# Qwiic_LoRa.net
KiCad netlist of a schematic drawn in EAGLE
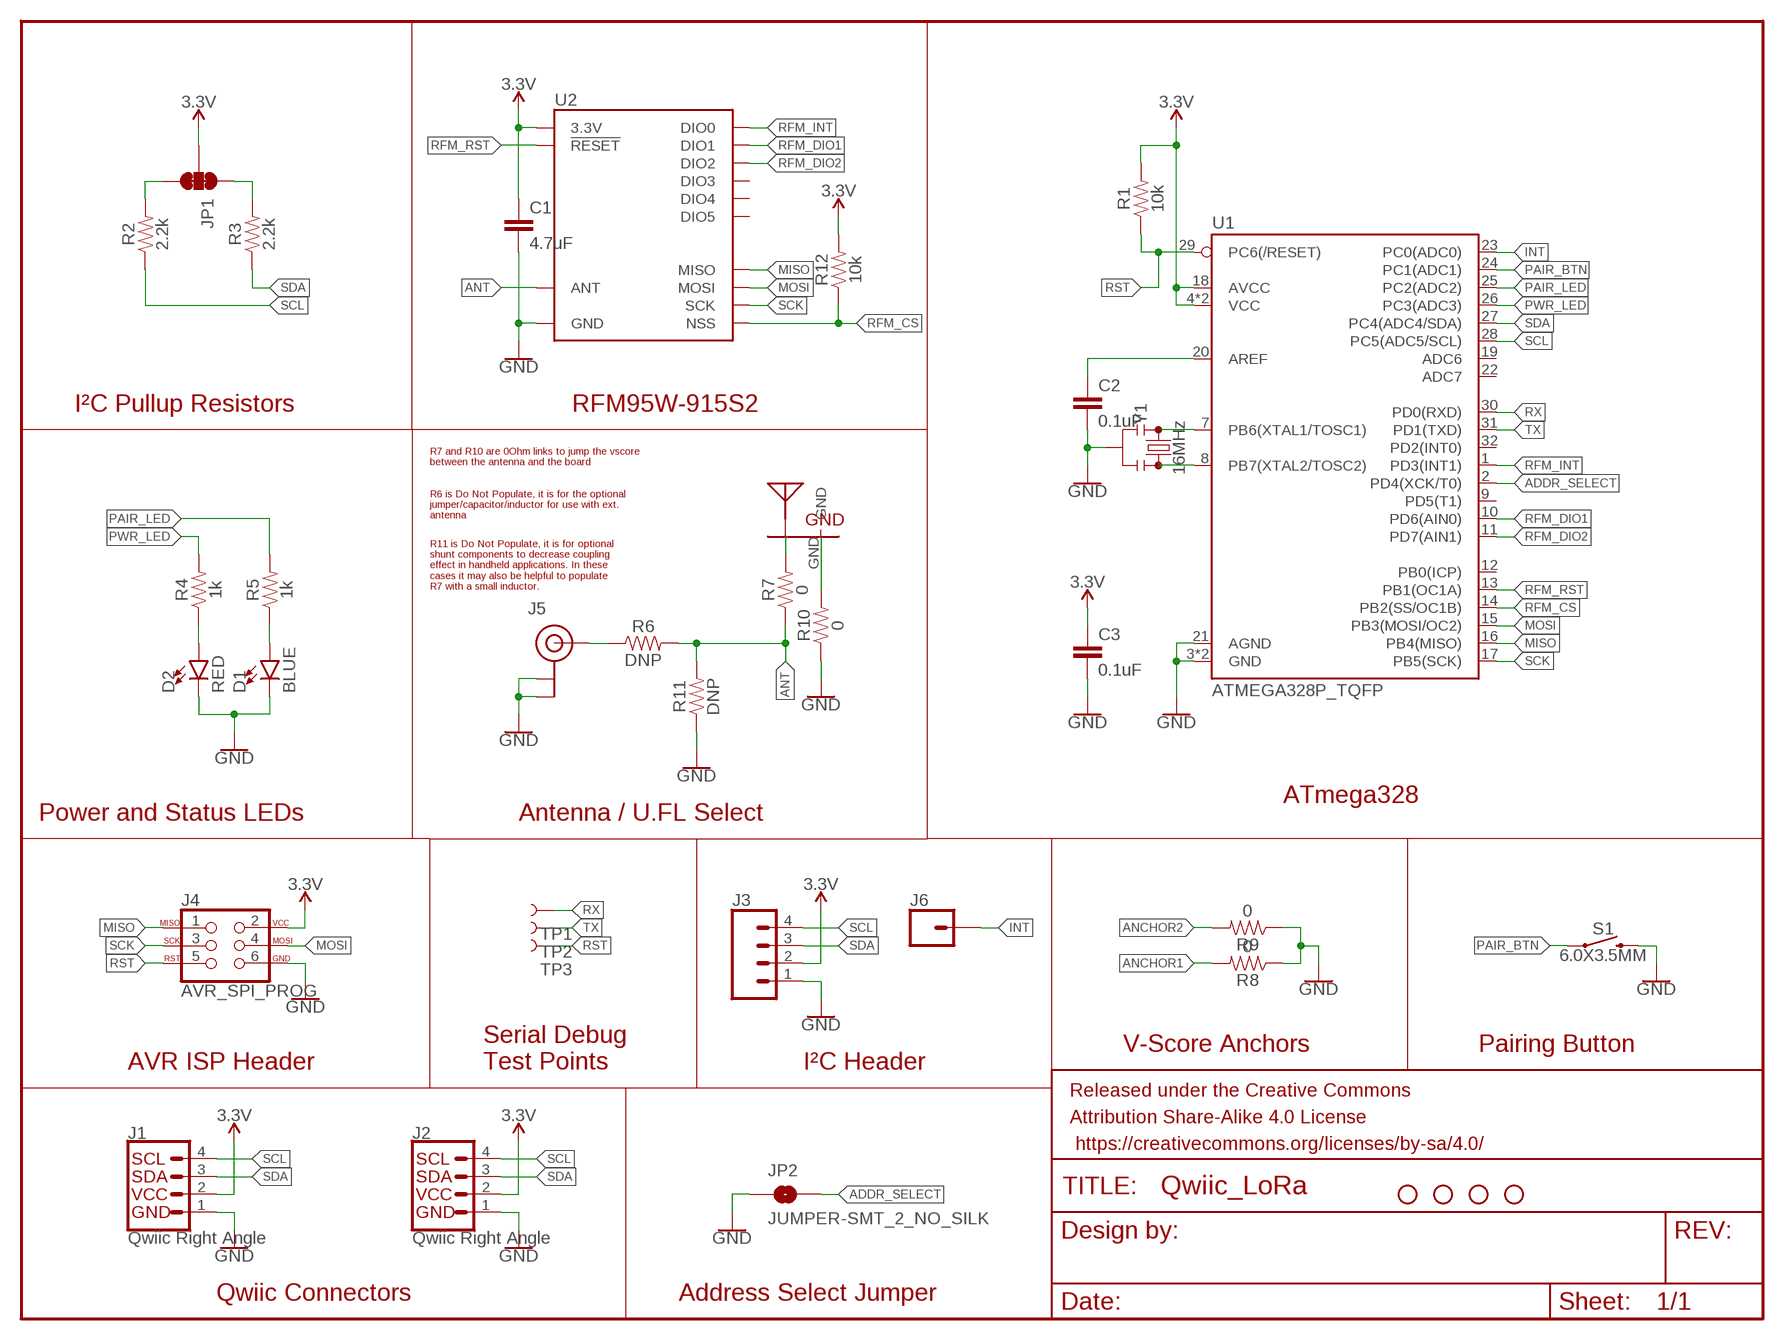
[diagram p0: schematic, sheet 1]

(export (version "E")
  (design (tool "Eeschema 10.0.6"))
  (components
    (comp (ref "C1")
      (value "4.7uF")
      (footprint "eagle-import:0603")
      (libsource (lib "eagle-import") (part "4.7UF0603"))
    )
    (comp (ref "C2")
      (value "0.1uF")
      (footprint "eagle-import:0603")
      (libsource (lib "eagle-import") (part "0.1UF-0603-25V-(+80/-20%)"))
    )
    (comp (ref "C3")
      (value "0.1uF")
      (footprint "eagle-import:0603")
      (libsource (lib "eagle-import") (part "0.1UF-0603-25V-(+80/-20%)"))
    )
    (comp (ref "D1")
      (value "BLUE")
      (footprint "eagle-import:LED-0603")
      (libsource (lib "eagle-import") (part "LED-BLUE0603"))
    )
    (comp (ref "D2")
      (value "RED")
      (footprint "eagle-import:LED-0603")
      (libsource (lib "eagle-import") (part "LED-RED0603"))
    )
    (comp (ref "FRAME1")
      (value "FRAME-LETTER")
      (footprint "eagle-import:CREATIVE_COMMONS")
      (libsource (lib "eagle-import") (part "FRAME-LETTER"))
    )
    (comp (ref "H1")
      (value "STAND-OFF")
      (footprint "eagle-import:STAND-OFF")
      (libsource (lib "eagle-import") (part "STAND-OFF"))
    )
    (comp (ref "H2")
      (value "STAND-OFF")
      (footprint "eagle-import:STAND-OFF")
      (libsource (lib "eagle-import") (part "STAND-OFF"))
    )
    (comp (ref "H3")
      (value "STAND-OFF")
      (footprint "eagle-import:STAND-OFF")
      (libsource (lib "eagle-import") (part "STAND-OFF"))
    )
    (comp (ref "H4")
      (value "STAND-OFF")
      (footprint "eagle-import:STAND-OFF")
      (libsource (lib "eagle-import") (part "STAND-OFF"))
    )
    (comp (ref "J1")
      (value "Qwiic Right Angle")
      (footprint "eagle-import:1X04_1MM_RA")
      (libsource (lib "eagle-import") (part "I2C_STANDARDQWIIC"))
    )
    (comp (ref "J2")
      (value "Qwiic Right Angle")
      (footprint "eagle-import:1X04_1MM_RA")
      (libsource (lib "eagle-import") (part "I2C_STANDARDQWIIC"))
    )
    (comp (ref "J3")
      (value "CONN_041X04_NO_SILK")
      (footprint "eagle-import:1X04_NO_SILK")
      (libsource (lib "eagle-import") (part "CONN_041X04_NO_SILK"))
    )
    (comp (ref "J4")
      (value "AVR_SPI_PROG")
      (footprint "eagle-import:2X3_TEST_POINTS")
      (libsource (lib "eagle-import") (part "AVR_SPI_PROG_3X2TESTPOINTS"))
    )
    (comp (ref "J5")
      (value "U.FL")
      (footprint "eagle-import:U.FL")
      (libsource (lib "eagle-import") (part "U.FL"))
    )
    (comp (ref "J6")
      (value "CONN_01PTH_NO_SILK_YES_STOP")
      (footprint "eagle-import:1X01_NO_SILK")
      (libsource (lib "eagle-import") (part "CONN_01PTH_NO_SILK_YES_STOP"))
    )
    (comp (ref "JP1")
      (value "JUMPER-SMT_3_2-NC_TRACE_SILK")
      (footprint "eagle-import:SMT-JUMPER_3_2-NC_TRACE_SILK")
      (libsource (lib "eagle-import") (part "JUMPER-SMT_3_2-NC_TRACE_SILK"))
    )
    (comp (ref "JP2")
      (value "JUMPER-SMT_2_NO_SILK")
      (footprint "eagle-import:SMT-JUMPER_2_NO_SILK")
      (libsource (lib "eagle-import") (part "JUMPER-SMT_2_NO_SILK"))
    )
    (comp (ref "R1")
      (value "10k")
      (footprint "eagle-import:0603")
      (libsource (lib "eagle-import") (part "10KOHM-0603-1/10W-1%"))
    )
    (comp (ref "R2")
      (value "2.2k")
      (footprint "eagle-import:0603")
      (libsource (lib "eagle-import") (part "2.2KOHM-0603-1/10W-1%"))
    )
    (comp (ref "R3")
      (value "2.2k")
      (footprint "eagle-import:0603")
      (libsource (lib "eagle-import") (part "2.2KOHM-0603-1/10W-1%"))
    )
    (comp (ref "R4")
      (value "1k")
      (footprint "eagle-import:0603")
      (libsource (lib "eagle-import") (part "1KOHM-0603-1/10W-1%"))
    )
    (comp (ref "R5")
      (value "1k")
      (footprint "eagle-import:0603")
      (libsource (lib "eagle-import") (part "1KOHM-0603-1/10W-1%"))
    )
    (comp (ref "R6")
      (value "DNP")
      (footprint "eagle-import:0603")
      (libsource (lib "eagle-import") (part "RESISTOR0603"))
    )
    (comp (ref "R7")
      (value "0")
      (footprint "eagle-import:0603")
      (libsource (lib "eagle-import") (part "RESISTOR0603"))
    )
    (comp (ref "R8")
      (value "0")
      (footprint "eagle-import:0603")
      (libsource (lib "eagle-import") (part "RESISTOR0603"))
    )
    (comp (ref "R9")
      (value "0")
      (footprint "eagle-import:0603")
      (libsource (lib "eagle-import") (part "RESISTOR0603"))
    )
    (comp (ref "R10")
      (value "0")
      (footprint "eagle-import:0603")
      (libsource (lib "eagle-import") (part "RESISTOR0603"))
    )
    (comp (ref "R11")
      (value "DNP")
      (footprint "eagle-import:0603")
      (libsource (lib "eagle-import") (part "RESISTOR0603"))
    )
    (comp (ref "R12")
      (value "10k")
      (footprint "eagle-import:0603")
      (libsource (lib "eagle-import") (part "10KOHM-0603-1/10W-1%"))
    )
    (comp (ref "S1")
      (value "6.0X3.5MM")
      (footprint "eagle-import:TACTILE_SWITCH_SMD_6.0X3.5MM")
      (libsource (lib "eagle-import") (part "MOMENTARY-SWITCH-SPST-SMD-6.0X3.5MM"))
    )
    (comp (ref "TP1")
      (value "TEST-POINT3")
      (footprint "eagle-import:PAD.03X.03")
      (libsource (lib "eagle-import") (part "TEST-POINT3"))
    )
    (comp (ref "TP2")
      (value "TEST-POINT3")
      (footprint "eagle-import:PAD.03X.03")
      (libsource (lib "eagle-import") (part "TEST-POINT3"))
    )
    (comp (ref "TP3")
      (value "TEST-POINT3")
      (footprint "eagle-import:PAD.03X.03")
      (libsource (lib "eagle-import") (part "TEST-POINT3"))
    )
    (comp (ref "U$1")
      (value "ANTENNA_915MHZ_INVERTED_F")
      (footprint "eagle-import:ANTENNA_INVERTED_F_915MHZ")
      (libsource (lib "eagle-import") (part "ANTENNA_915MHZ_INVERTED_F"))
    )
    (comp (ref "U1")
      (value "ATMEGA328P_TQFP")
      (footprint "eagle-import:TQFP32-08")
      (libsource (lib "eagle-import") (part "ATMEGA328P_TQFP"))
    )
    (comp (ref "U2")
      (value "RFM96W")
      (footprint "eagle-import:RFM95_96_97_98W")
      (libsource (lib "eagle-import") (part "RFM96W"))
    )
    (comp (ref "Y1")
      (value "16MHz")
      (footprint "eagle-import:RESONATOR-SMD-3.2X1.3")
      (libsource (lib "eagle-import") (part "RESONATOR-16MHZSMD_3.2X1.3"))
    )
  )
  (nets
    (net (code "1") (name "3.3V") (class "Default")
      (node (ref "C1") (pin "1") (pinfunction "1_1") (pintype "passive"))
      (node (ref "C3") (pin "1") (pinfunction "1_1") (pintype "passive"))
      (node (ref "J1") (pin "2") (pinfunction "2_2") (pintype "power_in"))
      (node (ref "J2") (pin "2") (pinfunction "2_2") (pintype "power_in"))
      (node (ref "J3") (pin "2") (pinfunction "2_2") (pintype "passive"))
      (node (ref "J4") (pin "2") (pinfunction "2_2") (pintype "passive"))
      (node (ref "JP1") (pin "2") (pinfunction "2_2") (pintype "passive"))
      (node (ref "R1") (pin "2") (pinfunction "2_2") (pintype "passive"))
      (node (ref "R12") (pin "2") (pinfunction "2_2") (pintype "passive"))
      (node (ref "U1") (pin "18") (pinfunction "AVCC_18") (pintype "bidirectional"))
      (node (ref "U1") (pin "4") (pinfunction "VCC_4") (pintype "bidirectional"))
      (node (ref "U1") (pin "6") (pinfunction "VCC_6") (pintype "bidirectional"))
      (node (ref "U2") (pin "3.3V") (pinfunction "3.3V_3.3V") (pintype "bidirectional"))
    )
    (net (code "2") (name "ADDR_SELECT") (class "Default")
      (node (ref "JP2") (pin "2") (pinfunction "2_2") (pintype "passive"))
      (node (ref "U1") (pin "2") (pinfunction "PD4(XCK/T0)_2") (pintype "bidirectional"))
    )
    (net (code "3") (name "ANCHOR1") (class "Default")
      (node (ref "R8") (pin "2") (pinfunction "2_2") (pintype "passive"))
    )
    (net (code "4") (name "ANCHOR2") (class "Default")
      (node (ref "R9") (pin "2") (pinfunction "2_2") (pintype "passive"))
    )
    (net (code "5") (name "ANT") (class "Default")
      (node (ref "R11") (pin "2") (pinfunction "2_2") (pintype "passive"))
      (node (ref "R6") (pin "2") (pinfunction "2_2") (pintype "passive"))
      (node (ref "R7") (pin "1") (pinfunction "1_1") (pintype "passive"))
      (node (ref "U2") (pin "ANT") (pinfunction "ANT_ANT") (pintype "bidirectional"))
    )
    (net (code "6") (name "GND") (class "Default")
      (node (ref "C1") (pin "2") (pinfunction "2_2") (pintype "passive"))
      (node (ref "C2") (pin "2") (pinfunction "2_2") (pintype "passive"))
      (node (ref "C3") (pin "2") (pinfunction "2_2") (pintype "passive"))
      (node (ref "D1") (pin "C") (pinfunction "C_C") (pintype "passive"))
      (node (ref "D2") (pin "C") (pinfunction "C_C") (pintype "passive"))
      (node (ref "J1") (pin "1") (pinfunction "1_1") (pintype "power_in"))
      (node (ref "J2") (pin "1") (pinfunction "1_1") (pintype "power_in"))
      (node (ref "J3") (pin "1") (pinfunction "1_1") (pintype "passive"))
      (node (ref "J4") (pin "6") (pinfunction "6_6") (pintype "passive"))
      (node (ref "J5") (pin "1") (pinfunction "GND_1") (pintype "bidirectional"))
      (node (ref "J5") (pin "2") (pinfunction "GND_2") (pintype "bidirectional"))
      (node (ref "JP2") (pin "1") (pinfunction "1_1") (pintype "passive"))
      (node (ref "R10") (pin "1") (pinfunction "1_1") (pintype "passive"))
      (node (ref "R11") (pin "1") (pinfunction "1_1") (pintype "passive"))
      (node (ref "R8") (pin "1") (pinfunction "1_1") (pintype "passive"))
      (node (ref "R9") (pin "1") (pinfunction "1_1") (pintype "passive"))
      (node (ref "S1") (pin "2") (pinfunction "2_2") (pintype "passive"))
      (node (ref "U1") (pin "21") (pinfunction "AGND_21") (pintype "bidirectional"))
      (node (ref "U1") (pin "3") (pinfunction "GND_3") (pintype "bidirectional"))
      (node (ref "U1") (pin "5") (pinfunction "GND_5") (pintype "bidirectional"))
      (node (ref "U2") (pin "GND@1") (pinfunction "GND_GND@1") (pintype "bidirectional"))
      (node (ref "U2") (pin "GND@2") (pinfunction "GND_GND@2") (pintype "bidirectional"))
      (node (ref "U2") (pin "GND@3") (pinfunction "GND_GND@3") (pintype "bidirectional"))
      (node (ref "Y1") (pin "2") (pinfunction "2_2") (pintype "passive"))
    )
    (net (code "7") (name "INT") (class "Default")
      (node (ref "J6") (pin "1") (pinfunction "1_1") (pintype "passive"))
      (node (ref "U1") (pin "23") (pinfunction "PC0(ADC0)_23") (pintype "bidirectional"))
    )
    (net (code "8") (name "MISO") (class "Default")
      (node (ref "J4") (pin "1") (pinfunction "1_1") (pintype "passive"))
      (node (ref "U1") (pin "16") (pinfunction "PB4(MISO)_16") (pintype "bidirectional"))
      (node (ref "U2") (pin "MISO") (pinfunction "MISO_MISO") (pintype "bidirectional"))
    )
    (net (code "9") (name "MOSI") (class "Default")
      (node (ref "J4") (pin "4") (pinfunction "4_4") (pintype "passive"))
      (node (ref "U1") (pin "15") (pinfunction "PB3(MOSI/OC2)_15") (pintype "bidirectional"))
      (node (ref "U2") (pin "MOSI") (pinfunction "MOSI_MOSI") (pintype "bidirectional"))
    )
    (net (code "10") (name "Net-(D1-PadA)") (class "Default")
      (node (ref "D1") (pin "A") (pinfunction "A_A") (pintype "passive"))
      (node (ref "R5") (pin "1") (pinfunction "1_1") (pintype "passive"))
    )
    (net (code "11") (name "Net-(D2-PadA)") (class "Default")
      (node (ref "D2") (pin "A") (pinfunction "A_A") (pintype "passive"))
      (node (ref "R4") (pin "1") (pinfunction "1_1") (pintype "passive"))
    )
    (net (code "12") (name "Net-(J5-SIGNAL)") (class "Default")
      (node (ref "J5") (pin "FEED") (pinfunction "SIGNAL_FEED") (pintype "bidirectional"))
      (node (ref "R6") (pin "1") (pinfunction "1_1") (pintype "passive"))
    )
    (net (code "13") (name "Net-(JP1-Pad1)") (class "Default")
      (node (ref "JP1") (pin "1") (pinfunction "1_1") (pintype "passive"))
      (node (ref "R3") (pin "2") (pinfunction "2_2") (pintype "passive"))
    )
    (net (code "14") (name "Net-(JP1-Pad3)") (class "Default")
      (node (ref "JP1") (pin "3") (pinfunction "3_3") (pintype "passive"))
      (node (ref "R2") (pin "2") (pinfunction "2_2") (pintype "passive"))
    )
    (net (code "15") (name "Net-(R7-Pad2)") (class "Default")
      (node (ref "R7") (pin "2") (pinfunction "2_2") (pintype "passive"))
      (node (ref "U$1") (pin "FEED") (pinfunction "FEED_FEED") (pintype "bidirectional"))
    )
    (net (code "16") (name "Net-(R10-Pad2)") (class "Default")
      (node (ref "R10") (pin "2") (pinfunction "2_2") (pintype "passive"))
      (node (ref "U$1") (pin "GND") (pinfunction "GND_GND") (pintype "bidirectional"))
    )
    (net (code "17") (name "Net-(U1-AREF)") (class "Default")
      (node (ref "C2") (pin "1") (pinfunction "1_1") (pintype "passive"))
      (node (ref "U1") (pin "20") (pinfunction "AREF_20") (pintype "bidirectional"))
    )
    (net (code "18") (name "Net-(U1-PB6(XTAL1{slash}TOSC1))") (class "Default")
      (node (ref "U1") (pin "7") (pinfunction "PB6(XTAL1/TOSC1)_7") (pintype "bidirectional"))
      (node (ref "Y1") (pin "1") (pinfunction "1_1") (pintype "passive"))
    )
    (net (code "19") (name "Net-(U1-PB7(XTAL2{slash}TOSC2))") (class "Default")
      (node (ref "U1") (pin "8") (pinfunction "PB7(XTAL2/TOSC2)_8") (pintype "bidirectional"))
      (node (ref "Y1") (pin "3") (pinfunction "3_3") (pintype "passive"))
    )
    (net (code "20") (name "PAIR_BTN") (class "Default")
      (node (ref "S1") (pin "1") (pinfunction "1_1") (pintype "passive"))
      (node (ref "U1") (pin "24") (pinfunction "PC1(ADC1)_24") (pintype "bidirectional"))
    )
    (net (code "21") (name "PAIR_LED") (class "Default")
      (node (ref "R5") (pin "2") (pinfunction "2_2") (pintype "passive"))
      (node (ref "U1") (pin "25") (pinfunction "PC2(ADC2)_25") (pintype "bidirectional"))
    )
    (net (code "22") (name "PWR_LED") (class "Default")
      (node (ref "R4") (pin "2") (pinfunction "2_2") (pintype "passive"))
      (node (ref "U1") (pin "26") (pinfunction "PC3(ADC3)_26") (pintype "bidirectional"))
    )
    (net (code "23") (name "RFM_CS") (class "Default")
      (node (ref "R12") (pin "1") (pinfunction "1_1") (pintype "passive"))
      (node (ref "U1") (pin "14") (pinfunction "PB2(SS/OC1B)_14") (pintype "bidirectional"))
      (node (ref "U2") (pin "NSS") (pinfunction "NSS_NSS") (pintype "bidirectional"))
    )
    (net (code "24") (name "RFM_DIO1") (class "Default")
      (node (ref "U1") (pin "10") (pinfunction "PD6(AIN0)_10") (pintype "bidirectional"))
      (node (ref "U2") (pin "DIO1") (pinfunction "DIO1_DIO1") (pintype "bidirectional"))
    )
    (net (code "25") (name "RFM_DIO2") (class "Default")
      (node (ref "U1") (pin "11") (pinfunction "PD7(AIN1)_11") (pintype "bidirectional"))
      (node (ref "U2") (pin "DIO2") (pinfunction "DIO2_DIO2") (pintype "bidirectional"))
    )
    (net (code "26") (name "RFM_INT") (class "Default")
      (node (ref "U1") (pin "1") (pinfunction "PD3(INT1)_1") (pintype "bidirectional"))
      (node (ref "U2") (pin "DIO0") (pinfunction "DIO0_DIO0") (pintype "bidirectional"))
    )
    (net (code "27") (name "RFM_RST") (class "Default")
      (node (ref "U1") (pin "13") (pinfunction "PB1(OC1A)_13") (pintype "bidirectional"))
      (node (ref "U2") (pin "!RESET") (pinfunction "~{RESET}_!RESET") (pintype "bidirectional"))
    )
    (net (code "28") (name "RST") (class "Default")
      (node (ref "J4") (pin "5") (pinfunction "5_5") (pintype "passive"))
      (node (ref "R1") (pin "1") (pinfunction "1_1") (pintype "passive"))
      (node (ref "TP3") (pin "P$1") (pinfunction "1_P$1") (pintype "bidirectional"))
      (node (ref "U1") (pin "29") (pinfunction "PC6(/RESET)_29") (pintype "bidirectional"))
    )
    (net (code "29") (name "RX") (class "Default")
      (node (ref "TP1") (pin "P$1") (pinfunction "1_P$1") (pintype "bidirectional"))
      (node (ref "U1") (pin "30") (pinfunction "PD0(RXD)_30") (pintype "bidirectional"))
    )
    (net (code "30") (name "SCK") (class "Default")
      (node (ref "J4") (pin "3") (pinfunction "3_3") (pintype "passive"))
      (node (ref "U1") (pin "17") (pinfunction "PB5(SCK)_17") (pintype "bidirectional"))
      (node (ref "U2") (pin "SCK") (pinfunction "SCK_SCK") (pintype "bidirectional"))
    )
    (net (code "31") (name "SCL") (class "Default")
      (node (ref "J1") (pin "4") (pinfunction "4_4") (pintype "passive"))
      (node (ref "J2") (pin "4") (pinfunction "4_4") (pintype "passive"))
      (node (ref "J3") (pin "4") (pinfunction "4_4") (pintype "passive"))
      (node (ref "R2") (pin "1") (pinfunction "1_1") (pintype "passive"))
      (node (ref "U1") (pin "28") (pinfunction "PC5(ADC5/SCL)_28") (pintype "bidirectional"))
    )
    (net (code "32") (name "SDA") (class "Default")
      (node (ref "J1") (pin "3") (pinfunction "3_3") (pintype "passive"))
      (node (ref "J2") (pin "3") (pinfunction "3_3") (pintype "passive"))
      (node (ref "J3") (pin "3") (pinfunction "3_3") (pintype "passive"))
      (node (ref "R3") (pin "1") (pinfunction "1_1") (pintype "passive"))
      (node (ref "U1") (pin "27") (pinfunction "PC4(ADC4/SDA)_27") (pintype "bidirectional"))
    )
    (net (code "33") (name "TX") (class "Default")
      (node (ref "TP2") (pin "P$1") (pinfunction "1_P$1") (pintype "bidirectional"))
      (node (ref "U1") (pin "31") (pinfunction "PD1(TXD)_31") (pintype "bidirectional"))
    )
    (net (code "34") (name "unconnected-(U1-ADC6-Pad19)") (class "Default")
      (node (ref "U1") (pin "19") (pinfunction "ADC6_19") (pintype "bidirectional"))
    )
    (net (code "35") (name "unconnected-(U1-ADC7-Pad22)") (class "Default")
      (node (ref "U1") (pin "22") (pinfunction "ADC7_22") (pintype "bidirectional"))
    )
    (net (code "36") (name "unconnected-(U1-PB0(ICP)-Pad12)") (class "Default")
      (node (ref "U1") (pin "12") (pinfunction "PB0(ICP)_12") (pintype "bidirectional"))
    )
    (net (code "37") (name "unconnected-(U1-PD2(INT0)-Pad32)") (class "Default")
      (node (ref "U1") (pin "32") (pinfunction "PD2(INT0)_32") (pintype "bidirectional"))
    )
    (net (code "38") (name "unconnected-(U1-PD5(T1)-Pad9)") (class "Default")
      (node (ref "U1") (pin "9") (pinfunction "PD5(T1)_9") (pintype "bidirectional"))
    )
    (net (code "39") (name "unconnected-(U2-PadDIO3)") (class "Default")
      (node (ref "U2") (pin "DIO3") (pinfunction "DIO3_DIO3") (pintype "bidirectional"))
    )
    (net (code "40") (name "unconnected-(U2-PadDIO4)") (class "Default")
      (node (ref "U2") (pin "DIO4") (pinfunction "DIO4_DIO4") (pintype "bidirectional"))
    )
    (net (code "41") (name "unconnected-(U2-PadDIO5)") (class "Default")
      (node (ref "U2") (pin "DIO5") (pinfunction "DIO5_DIO5") (pintype "bidirectional"))
    )
  )
)
